# ffboard_adapter.net
KiCad netlist of a schematic drawn in EAGLE
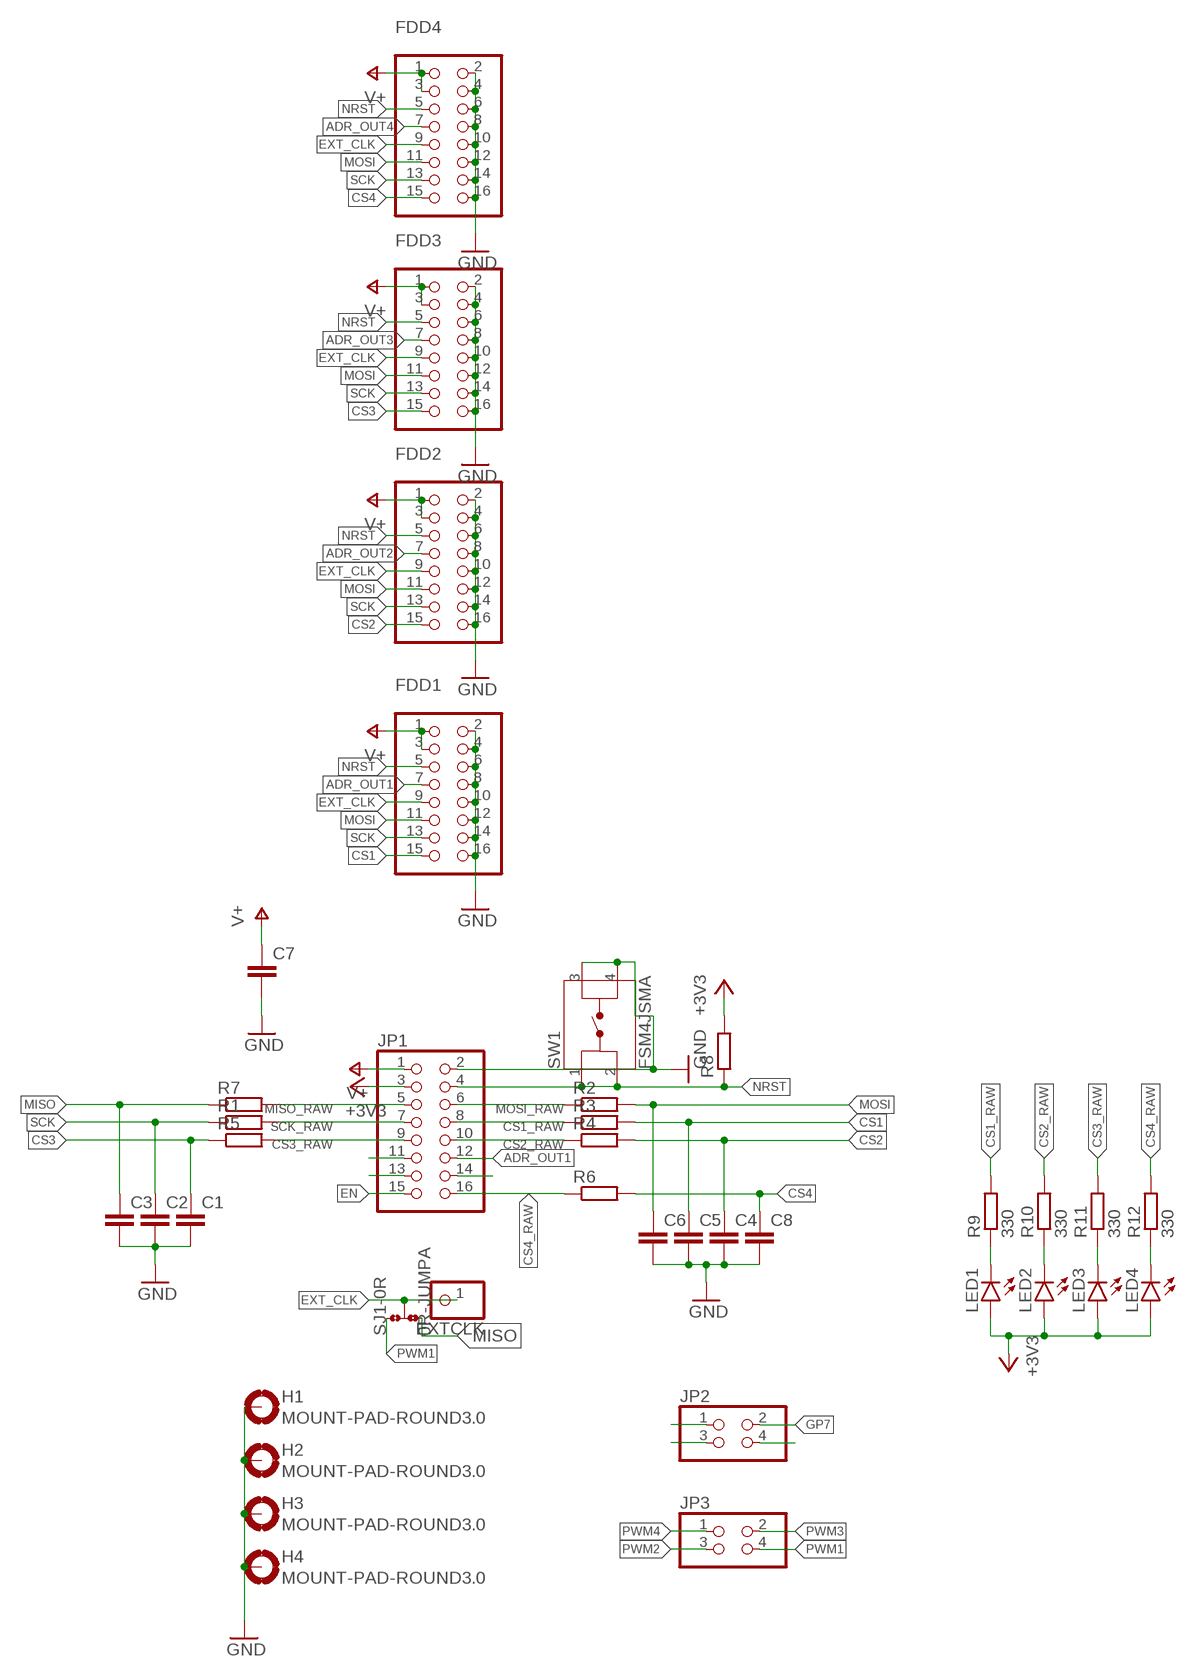
[diagram p0: schematic, sheet 1]

(export (version "E")
  (design (tool "Eeschema 10.0.6"))
  (components
    (comp (ref "C1")
      (value "C-EUC0603")
      (footprint "eagle-import:C0603")
      (libsource (lib "eagle-import") (part "C-EUC0603"))
    )
    (comp (ref "C2")
      (value "C-EUC0603")
      (footprint "eagle-import:C0603")
      (libsource (lib "eagle-import") (part "C-EUC0603"))
    )
    (comp (ref "C3")
      (value "C-EUC0603")
      (footprint "eagle-import:C0603")
      (libsource (lib "eagle-import") (part "C-EUC0603"))
    )
    (comp (ref "C4")
      (value "C-EUC0603")
      (footprint "eagle-import:C0603")
      (libsource (lib "eagle-import") (part "C-EUC0603"))
    )
    (comp (ref "C5")
      (value "C-EUC0603")
      (footprint "eagle-import:C0603")
      (libsource (lib "eagle-import") (part "C-EUC0603"))
    )
    (comp (ref "C6")
      (value "C-EUC0603")
      (footprint "eagle-import:C0603")
      (libsource (lib "eagle-import") (part "C-EUC0603"))
    )
    (comp (ref "C7")
      (value "C-EUC0603")
      (footprint "eagle-import:C0603")
      (libsource (lib "eagle-import") (part "C-EUC0603"))
    )
    (comp (ref "C8")
      (value "C-EUC0603")
      (footprint "eagle-import:C0603")
      (libsource (lib "eagle-import") (part "C-EUC0603"))
    )
    (comp (ref "EXTCLK")
      (value "PINHD-1X1")
      (footprint "eagle-import:1X01")
      (libsource (lib "eagle-import") (part "PINHD-1X1"))
    )
    (comp (ref "FDD1")
      (value "C221085")
      (footprint "eagle-import:2X08")
      (libsource (lib "eagle-import") (part "PINHD-2X8"))
    )
    (comp (ref "FDD2")
      (value "C221085")
      (footprint "eagle-import:2X08")
      (libsource (lib "eagle-import") (part "PINHD-2X8"))
    )
    (comp (ref "FDD3")
      (value "C221085")
      (footprint "eagle-import:2X08")
      (libsource (lib "eagle-import") (part "PINHD-2X8"))
    )
    (comp (ref "FDD4")
      (value "C221085")
      (footprint "eagle-import:2X08")
      (libsource (lib "eagle-import") (part "PINHD-2X8"))
    )
    (comp (ref "H1")
      (value "MOUNT-PAD-ROUND3.0")
      (footprint "eagle-import:3,0-PAD")
      (libsource (lib "eagle-import") (part "MOUNT-PAD-ROUND3.0"))
    )
    (comp (ref "H2")
      (value "MOUNT-PAD-ROUND3.0")
      (footprint "eagle-import:3,0-PAD")
      (libsource (lib "eagle-import") (part "MOUNT-PAD-ROUND3.0"))
    )
    (comp (ref "H3")
      (value "MOUNT-PAD-ROUND3.0")
      (footprint "eagle-import:3,0-PAD")
      (libsource (lib "eagle-import") (part "MOUNT-PAD-ROUND3.0"))
    )
    (comp (ref "H4")
      (value "MOUNT-PAD-ROUND3.0")
      (footprint "eagle-import:3,0-PAD")
      (libsource (lib "eagle-import") (part "MOUNT-PAD-ROUND3.0"))
    )
    (comp (ref "JP1")
      (value "PINHD-2X8")
      (footprint "eagle-import:2X08")
      (libsource (lib "eagle-import") (part "PINHD-2X8"))
    )
    (comp (ref "JP2")
      (value "PINHD-2X2")
      (footprint "eagle-import:2X02")
      (libsource (lib "eagle-import") (part "PINHD-2X2"))
    )
    (comp (ref "JP3")
      (value "PINHD-2X2")
      (footprint "eagle-import:2X02")
      (libsource (lib "eagle-import") (part "PINHD-2X2"))
    )
    (comp (ref "LED1")
      (value "LEDSML0805")
      (footprint "eagle-import:SML0805")
      (libsource (lib "eagle-import") (part "LEDSML0805"))
    )
    (comp (ref "LED2")
      (value "LEDSML0805")
      (footprint "eagle-import:SML0805")
      (libsource (lib "eagle-import") (part "LEDSML0805"))
    )
    (comp (ref "LED3")
      (value "LEDSML0805")
      (footprint "eagle-import:SML0805")
      (libsource (lib "eagle-import") (part "LEDSML0805"))
    )
    (comp (ref "LED4")
      (value "LEDSML0805")
      (footprint "eagle-import:SML0805")
      (libsource (lib "eagle-import") (part "LEDSML0805"))
    )
    (comp (ref "R1")
      (value "R-EU_R0603")
      (footprint "eagle-import:R0603")
      (libsource (lib "eagle-import") (part "R-EU_R0603"))
    )
    (comp (ref "R2")
      (value "R-EU_R0603")
      (footprint "eagle-import:R0603")
      (libsource (lib "eagle-import") (part "R-EU_R0603"))
    )
    (comp (ref "R3")
      (value "R-EU_R0603")
      (footprint "eagle-import:R0603")
      (libsource (lib "eagle-import") (part "R-EU_R0603"))
    )
    (comp (ref "R4")
      (value "R-EU_R0603")
      (footprint "eagle-import:R0603")
      (libsource (lib "eagle-import") (part "R-EU_R0603"))
    )
    (comp (ref "R5")
      (value "R-EU_R0603")
      (footprint "eagle-import:R0603")
      (libsource (lib "eagle-import") (part "R-EU_R0603"))
    )
    (comp (ref "R6")
      (value "R-EU_R0603")
      (footprint "eagle-import:R0603")
      (libsource (lib "eagle-import") (part "R-EU_R0603"))
    )
    (comp (ref "R7")
      (value "R-EU_R0603")
      (footprint "eagle-import:R0603")
      (libsource (lib "eagle-import") (part "R-EU_R0603"))
    )
    (comp (ref "R8")
      (value "R-EU_R0603")
      (footprint "eagle-import:R0603")
      (libsource (lib "eagle-import") (part "R-EU_R0603"))
    )
    (comp (ref "R9")
      (value "330")
      (footprint "eagle-import:R0603")
      (libsource (lib "eagle-import") (part "R-EU_R0603"))
    )
    (comp (ref "R10")
      (value "330")
      (footprint "eagle-import:R0603")
      (libsource (lib "eagle-import") (part "R-EU_R0603"))
    )
    (comp (ref "R11")
      (value "330")
      (footprint "eagle-import:R0603")
      (libsource (lib "eagle-import") (part "R-EU_R0603"))
    )
    (comp (ref "R12")
      (value "330")
      (footprint "eagle-import:R0603")
      (libsource (lib "eagle-import") (part "R-EU_R0603"))
    )
    (comp (ref "SJ1")
      (value "0R-JUMPA")
      (footprint "eagle-import:A0R-JMP")
      (libsource (lib "eagle-import") (part "0R-JUMPA"))
    )
    (comp (ref "SW1")
      (value "FSM4JSMA")
      (footprint "eagle-import:FSM4JSMA")
      (fields
        (field (name "DIGIKEY_PART_NUMBER") "450-1129-ND")
        (field (name "MANUFACTURER") "TE Connectivity ALCOSWITCH Switches")
        (field (name "CREATED_BY") "PCBLayout.com")
      )
      (libsource (lib "eagle-import") (part "FSM4JSMA"))
    )
  )
  (nets
    (net (code "1") (name "+3V3") (class "Default")
      (node (ref "JP1") (pin "3") (pinfunction "3_3") (pintype "passive"))
      (node (ref "LED1") (pin "A") (pinfunction "A_A") (pintype "passive"))
      (node (ref "LED2") (pin "A") (pinfunction "A_A") (pintype "passive"))
      (node (ref "LED3") (pin "A") (pinfunction "A_A") (pintype "passive"))
      (node (ref "LED4") (pin "A") (pinfunction "A_A") (pintype "passive"))
      (node (ref "R8") (pin "2") (pinfunction "2_2") (pintype "passive"))
    )
    (net (code "2") (name "/MISO_RAW") (class "Default")
      (node (ref "JP1") (pin "5") (pinfunction "5_5") (pintype "passive"))
      (node (ref "R7") (pin "2") (pinfunction "2_2") (pintype "passive"))
    )
    (net (code "3") (name "/MOSI_RAW") (class "Default")
      (node (ref "JP1") (pin "6") (pinfunction "6_6") (pintype "passive"))
      (node (ref "R2") (pin "1") (pinfunction "1_1") (pintype "passive"))
    )
    (net (code "4") (name "/SCK_RAW") (class "Default")
      (node (ref "JP1") (pin "7") (pinfunction "7_7") (pintype "passive"))
      (node (ref "R1") (pin "2") (pinfunction "2_2") (pintype "passive"))
    )
    (net (code "5") (name "ADR_OUT1") (class "Default")
      (node (ref "FDD1") (pin "7") (pinfunction "7_7") (pintype "passive"))
      (node (ref "JP1") (pin "12") (pinfunction "12_12") (pintype "passive"))
    )
    (net (code "6") (name "ADR_OUT2") (class "Default")
      (node (ref "FDD2") (pin "7") (pinfunction "7_7") (pintype "passive"))
    )
    (net (code "7") (name "ADR_OUT3") (class "Default")
      (node (ref "FDD3") (pin "7") (pinfunction "7_7") (pintype "passive"))
    )
    (net (code "8") (name "ADR_OUT4") (class "Default")
      (node (ref "FDD4") (pin "7") (pinfunction "7_7") (pintype "passive"))
    )
    (net (code "9") (name "CS1") (class "Default")
      (node (ref "C5") (pin "1") (pinfunction "1_1") (pintype "passive"))
      (node (ref "FDD1") (pin "15") (pinfunction "15_15") (pintype "passive"))
      (node (ref "R3") (pin "2") (pinfunction "2_2") (pintype "passive"))
    )
    (net (code "10") (name "CS1_RAW") (class "Default")
      (node (ref "JP1") (pin "8") (pinfunction "8_8") (pintype "passive"))
      (node (ref "R3") (pin "1") (pinfunction "1_1") (pintype "passive"))
      (node (ref "R9") (pin "2") (pinfunction "2_2") (pintype "passive"))
    )
    (net (code "11") (name "CS2") (class "Default")
      (node (ref "C4") (pin "1") (pinfunction "1_1") (pintype "passive"))
      (node (ref "FDD2") (pin "15") (pinfunction "15_15") (pintype "passive"))
      (node (ref "R4") (pin "2") (pinfunction "2_2") (pintype "passive"))
    )
    (net (code "12") (name "CS2_RAW") (class "Default")
      (node (ref "JP1") (pin "10") (pinfunction "10_10") (pintype "passive"))
      (node (ref "R10") (pin "2") (pinfunction "2_2") (pintype "passive"))
      (node (ref "R4") (pin "1") (pinfunction "1_1") (pintype "passive"))
    )
    (net (code "13") (name "CS3") (class "Default")
      (node (ref "C1") (pin "1") (pinfunction "1_1") (pintype "passive"))
      (node (ref "FDD3") (pin "15") (pinfunction "15_15") (pintype "passive"))
      (node (ref "R5") (pin "1") (pinfunction "1_1") (pintype "passive"))
    )
    (net (code "14") (name "CS3_RAW") (class "Default")
      (node (ref "JP1") (pin "9") (pinfunction "9_9") (pintype "passive"))
      (node (ref "R11") (pin "2") (pinfunction "2_2") (pintype "passive"))
      (node (ref "R5") (pin "2") (pinfunction "2_2") (pintype "passive"))
    )
    (net (code "15") (name "CS4") (class "Default")
      (node (ref "C8") (pin "1") (pinfunction "1_1") (pintype "passive"))
      (node (ref "FDD4") (pin "15") (pinfunction "15_15") (pintype "passive"))
      (node (ref "R6") (pin "2") (pinfunction "2_2") (pintype "passive"))
    )
    (net (code "16") (name "CS4_RAW") (class "Default")
      (node (ref "JP1") (pin "16") (pinfunction "16_16") (pintype "passive"))
      (node (ref "R12") (pin "2") (pinfunction "2_2") (pintype "passive"))
      (node (ref "R6") (pin "1") (pinfunction "1_1") (pintype "passive"))
    )
    (net (code "17") (name "EN") (class "Default")
      (node (ref "JP1") (pin "15") (pinfunction "15_15") (pintype "passive"))
    )
    (net (code "18") (name "EXT_CLK") (class "Default")
      (node (ref "EXTCLK") (pin "1") (pinfunction "1_1") (pintype "passive"))
      (node (ref "FDD1") (pin "9") (pinfunction "9_9") (pintype "passive"))
      (node (ref "FDD2") (pin "9") (pinfunction "9_9") (pintype "passive"))
      (node (ref "FDD3") (pin "9") (pinfunction "9_9") (pintype "passive"))
      (node (ref "FDD4") (pin "9") (pinfunction "9_9") (pintype "passive"))
      (node (ref "SJ1") (pin "2") (pinfunction "2_2") (pintype "passive"))
    )
    (net (code "19") (name "GND") (class "Default")
      (node (ref "C1") (pin "2") (pinfunction "2_2") (pintype "passive"))
      (node (ref "C2") (pin "2") (pinfunction "2_2") (pintype "passive"))
      (node (ref "C3") (pin "2") (pinfunction "2_2") (pintype "passive"))
      (node (ref "C4") (pin "2") (pinfunction "2_2") (pintype "passive"))
      (node (ref "C5") (pin "2") (pinfunction "2_2") (pintype "passive"))
      (node (ref "C6") (pin "2") (pinfunction "2_2") (pintype "passive"))
      (node (ref "C7") (pin "2") (pinfunction "2_2") (pintype "passive"))
      (node (ref "C8") (pin "2") (pinfunction "2_2") (pintype "passive"))
      (node (ref "FDD1") (pin "10") (pinfunction "10_10") (pintype "passive"))
      (node (ref "FDD1") (pin "12") (pinfunction "12_12") (pintype "passive"))
      (node (ref "FDD1") (pin "14") (pinfunction "14_14") (pintype "passive"))
      (node (ref "FDD1") (pin "16") (pinfunction "16_16") (pintype "passive"))
      (node (ref "FDD1") (pin "2") (pinfunction "2_2") (pintype "passive"))
      (node (ref "FDD1") (pin "4") (pinfunction "4_4") (pintype "passive"))
      (node (ref "FDD1") (pin "6") (pinfunction "6_6") (pintype "passive"))
      (node (ref "FDD1") (pin "8") (pinfunction "8_8") (pintype "passive"))
      (node (ref "FDD2") (pin "10") (pinfunction "10_10") (pintype "passive"))
      (node (ref "FDD2") (pin "12") (pinfunction "12_12") (pintype "passive"))
      (node (ref "FDD2") (pin "14") (pinfunction "14_14") (pintype "passive"))
      (node (ref "FDD2") (pin "16") (pinfunction "16_16") (pintype "passive"))
      (node (ref "FDD2") (pin "2") (pinfunction "2_2") (pintype "passive"))
      (node (ref "FDD2") (pin "4") (pinfunction "4_4") (pintype "passive"))
      (node (ref "FDD2") (pin "6") (pinfunction "6_6") (pintype "passive"))
      (node (ref "FDD2") (pin "8") (pinfunction "8_8") (pintype "passive"))
      (node (ref "FDD3") (pin "10") (pinfunction "10_10") (pintype "passive"))
      (node (ref "FDD3") (pin "12") (pinfunction "12_12") (pintype "passive"))
      (node (ref "FDD3") (pin "14") (pinfunction "14_14") (pintype "passive"))
      (node (ref "FDD3") (pin "16") (pinfunction "16_16") (pintype "passive"))
      (node (ref "FDD3") (pin "2") (pinfunction "2_2") (pintype "passive"))
      (node (ref "FDD3") (pin "4") (pinfunction "4_4") (pintype "passive"))
      (node (ref "FDD3") (pin "6") (pinfunction "6_6") (pintype "passive"))
      (node (ref "FDD3") (pin "8") (pinfunction "8_8") (pintype "passive"))
      (node (ref "FDD4") (pin "10") (pinfunction "10_10") (pintype "passive"))
      (node (ref "FDD4") (pin "12") (pinfunction "12_12") (pintype "passive"))
      (node (ref "FDD4") (pin "14") (pinfunction "14_14") (pintype "passive"))
      (node (ref "FDD4") (pin "16") (pinfunction "16_16") (pintype "passive"))
      (node (ref "FDD4") (pin "2") (pinfunction "2_2") (pintype "passive"))
      (node (ref "FDD4") (pin "4") (pinfunction "4_4") (pintype "passive"))
      (node (ref "FDD4") (pin "6") (pinfunction "6_6") (pintype "passive"))
      (node (ref "FDD4") (pin "8") (pinfunction "8_8") (pintype "passive"))
      (node (ref "H1") (pin "B3,0") (pinfunction "MOUNT_B3,0") (pintype "passive"))
      (node (ref "H2") (pin "B3,0") (pinfunction "MOUNT_B3,0") (pintype "passive"))
      (node (ref "H3") (pin "B3,0") (pinfunction "MOUNT_B3,0") (pintype "passive"))
      (node (ref "H4") (pin "B3,0") (pinfunction "MOUNT_B3,0") (pintype "passive"))
      (node (ref "JP1") (pin "2") (pinfunction "2_2") (pintype "passive"))
      (node (ref "SW1") (pin "3") (pinfunction "3_3") (pintype "passive"))
      (node (ref "SW1") (pin "4") (pinfunction "4_4") (pintype "passive"))
    )
    (net (code "20") (name "GP7") (class "Default")
      (node (ref "JP2") (pin "2") (pinfunction "2_2") (pintype "passive"))
    )
    (net (code "21") (name "MISO") (class "Default")
      (node (ref "C3") (pin "1") (pinfunction "1_1") (pintype "passive"))
      (node (ref "R7") (pin "1") (pinfunction "1_1") (pintype "passive"))
      (node (ref "SJ1") (pin "3") (pinfunction "3_3") (pintype "passive"))
    )
    (net (code "22") (name "MOSI") (class "Default")
      (node (ref "C6") (pin "1") (pinfunction "1_1") (pintype "passive"))
      (node (ref "FDD1") (pin "11") (pinfunction "11_11") (pintype "passive"))
      (node (ref "FDD2") (pin "11") (pinfunction "11_11") (pintype "passive"))
      (node (ref "FDD3") (pin "11") (pinfunction "11_11") (pintype "passive"))
      (node (ref "FDD4") (pin "11") (pinfunction "11_11") (pintype "passive"))
      (node (ref "R2") (pin "2") (pinfunction "2_2") (pintype "passive"))
    )
    (net (code "23") (name "NRST") (class "Default")
      (node (ref "FDD1") (pin "5") (pinfunction "5_5") (pintype "passive"))
      (node (ref "FDD2") (pin "5") (pinfunction "5_5") (pintype "passive"))
      (node (ref "FDD3") (pin "5") (pinfunction "5_5") (pintype "passive"))
      (node (ref "FDD4") (pin "5") (pinfunction "5_5") (pintype "passive"))
      (node (ref "JP1") (pin "4") (pinfunction "4_4") (pintype "passive"))
      (node (ref "R8") (pin "1") (pinfunction "1_1") (pintype "passive"))
      (node (ref "SW1") (pin "1") (pinfunction "1_1") (pintype "passive"))
      (node (ref "SW1") (pin "2") (pinfunction "2_2") (pintype "passive"))
    )
    (net (code "24") (name "Net-(LED1-PadC)") (class "Default")
      (node (ref "LED1") (pin "C") (pinfunction "C_C") (pintype "passive"))
      (node (ref "R9") (pin "1") (pinfunction "1_1") (pintype "passive"))
    )
    (net (code "25") (name "Net-(LED2-PadC)") (class "Default")
      (node (ref "LED2") (pin "C") (pinfunction "C_C") (pintype "passive"))
      (node (ref "R10") (pin "1") (pinfunction "1_1") (pintype "passive"))
    )
    (net (code "26") (name "Net-(LED3-PadC)") (class "Default")
      (node (ref "LED3") (pin "C") (pinfunction "C_C") (pintype "passive"))
      (node (ref "R11") (pin "1") (pinfunction "1_1") (pintype "passive"))
    )
    (net (code "27") (name "Net-(LED4-PadC)") (class "Default")
      (node (ref "LED4") (pin "C") (pinfunction "C_C") (pintype "passive"))
      (node (ref "R12") (pin "1") (pinfunction "1_1") (pintype "passive"))
    )
    (net (code "28") (name "PWM1") (class "Default")
      (node (ref "JP3") (pin "4") (pinfunction "4_4") (pintype "passive"))
      (node (ref "SJ1") (pin "1") (pinfunction "1_1") (pintype "passive"))
    )
    (net (code "29") (name "PWM2") (class "Default")
      (node (ref "JP3") (pin "3") (pinfunction "3_3") (pintype "passive"))
    )
    (net (code "30") (name "PWM3") (class "Default")
      (node (ref "JP3") (pin "2") (pinfunction "2_2") (pintype "passive"))
    )
    (net (code "31") (name "PWM4") (class "Default")
      (node (ref "JP3") (pin "1") (pinfunction "1_1") (pintype "passive"))
    )
    (net (code "32") (name "SCK") (class "Default")
      (node (ref "C2") (pin "1") (pinfunction "1_1") (pintype "passive"))
      (node (ref "FDD1") (pin "13") (pinfunction "13_13") (pintype "passive"))
      (node (ref "FDD2") (pin "13") (pinfunction "13_13") (pintype "passive"))
      (node (ref "FDD3") (pin "13") (pinfunction "13_13") (pintype "passive"))
      (node (ref "FDD4") (pin "13") (pinfunction "13_13") (pintype "passive"))
      (node (ref "R1") (pin "1") (pinfunction "1_1") (pintype "passive"))
    )
    (net (code "33") (name "V+") (class "Default")
      (node (ref "C7") (pin "1") (pinfunction "1_1") (pintype "passive"))
      (node (ref "FDD1") (pin "1") (pinfunction "1_1") (pintype "passive"))
      (node (ref "FDD1") (pin "3") (pinfunction "3_3") (pintype "passive"))
      (node (ref "FDD2") (pin "1") (pinfunction "1_1") (pintype "passive"))
      (node (ref "FDD2") (pin "3") (pinfunction "3_3") (pintype "passive"))
      (node (ref "FDD3") (pin "1") (pinfunction "1_1") (pintype "passive"))
      (node (ref "FDD3") (pin "3") (pinfunction "3_3") (pintype "passive"))
      (node (ref "FDD4") (pin "1") (pinfunction "1_1") (pintype "passive"))
      (node (ref "FDD4") (pin "3") (pinfunction "3_3") (pintype "passive"))
      (node (ref "JP1") (pin "1") (pinfunction "1_1") (pintype "passive"))
    )
    (net (code "34") (name "unconnected-(JP1-Pad11)") (class "Default")
      (node (ref "JP1") (pin "11") (pinfunction "11_11") (pintype "passive"))
    )
    (net (code "35") (name "unconnected-(JP1-Pad13)") (class "Default")
      (node (ref "JP1") (pin "13") (pinfunction "13_13") (pintype "passive"))
    )
    (net (code "36") (name "unconnected-(JP1-Pad14)") (class "Default")
      (node (ref "JP1") (pin "14") (pinfunction "14_14") (pintype "passive"))
    )
    (net (code "37") (name "unconnected-(JP2-Pad1)") (class "Default")
      (node (ref "JP2") (pin "1") (pinfunction "1_1") (pintype "passive"))
    )
    (net (code "38") (name "unconnected-(JP2-Pad3)") (class "Default")
      (node (ref "JP2") (pin "3") (pinfunction "3_3") (pintype "passive"))
    )
    (net (code "39") (name "unconnected-(JP2-Pad4)") (class "Default")
      (node (ref "JP2") (pin "4") (pinfunction "4_4") (pintype "passive"))
    )
  )
)
